# cap_sense.net
KiCad netlist of a schematic drawn in Altium Designer
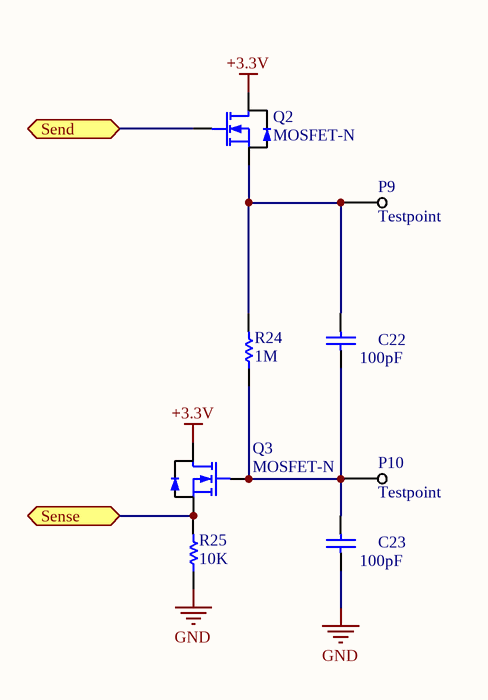
[diagram p0: cap_sense.SchDoc]

(export (version "E")
  (design (tool "Eeschema 10.0.6"))
  (components
    (comp (ref "C22")
      (value "100pF")
      (footprint "Miscellaneous Devices:1608[0603]")
      (description "Capacitor")
      (fields (field (name "Comment") "Cap") (field (name "PUBLISHER") "Altium Limited"))
      (libsource (lib "Schematic Lib") (part "Cap"))
    )
    (comp (ref "C23")
      (value "100pF")
      (footprint "Miscellaneous Devices:1608[0603]")
      (description "Capacitor")
      (fields (field (name "Comment") "Cap") (field (name "PUBLISHER") "Altium Limited"))
      (libsource (lib "Schematic Lib") (part "Cap"))
    )
    (comp (ref "P9")
      (value "Testpoint")
      (footprint "ELE3PRO_2012:Testpoint")
      (libsource (lib "Schematic Lib") (part "Testpoint"))
    )
    (comp (ref "P10")
      (value "Testpoint")
      (footprint "ELE3PRO_2012:Testpoint")
      (libsource (lib "Schematic Lib") (part "Testpoint"))
    )
    (comp (ref "Q2")
      (value "MOSFET-N")
      (footprint "ELE3PRO_2012:SOT23")
      (description "N-Channel MOSFET")
      (fields (field (name "PUBLISHER") "Altium Limited"))
      (libsource (lib "Schlib1") (part "MOSFET-N"))
    )
    (comp (ref "Q3")
      (value "MOSFET-N")
      (footprint "ELE3PRO_2012:SOT23")
      (description "N-Channel MOSFET")
      (fields (field (name "PUBLISHER") "Altium Limited"))
      (libsource (lib "Schlib1") (part "MOSFET-N"))
    )
    (comp (ref "R24")
      (value "1M")
      (footprint "J1-0603")
      (description "Resistor 0805")
      (fields (field (name "Comment") "Res") (field (name "PUBLISHER") "Altium Limited"))
      (libsource (lib "Schematic Lib") (part "Res"))
    )
    (comp (ref "R25")
      (value "10K")
      (footprint "J1-0603")
      (description "Resistor 0805")
      (fields (field (name "Comment") "Res") (field (name "PUBLISHER") "Altium Limited"))
      (libsource (lib "Schematic Lib") (part "Res"))
    )
  )
  (nets
    (net (code "1") (name "+3.3V") (class "Default")
      (node (ref "Q2") (pin "3") (pinfunction "D_3") (pintype "passive"))
      (node (ref "Q3") (pin "3") (pinfunction "D_3") (pintype "passive"))
    )
    (net (code "2") (name "/Send") (class "Default")
      (node (ref "Q2") (pin "1") (pinfunction "G_1") (pintype "passive"))
    )
    (net (code "3") (name "/Sense") (class "Default")
      (node (ref "Q3") (pin "2") (pinfunction "S_2") (pintype "passive"))
      (node (ref "R25") (pin "2") (pinfunction "2_2") (pintype "passive"))
    )
    (net (code "4") (name "GND") (class "Default")
      (node (ref "C23") (pin "2") (pinfunction "2_2") (pintype "passive"))
      (node (ref "R25") (pin "1") (pinfunction "1_1") (pintype "passive"))
    )
    (net (code "5") (name "Net-(Q2-S)") (class "Default")
      (node (ref "C22") (pin "1") (pinfunction "1_1") (pintype "passive"))
      (node (ref "P9") (pin "1") (pinfunction "1_1") (pintype "passive"))
      (node (ref "Q2") (pin "2") (pinfunction "S_2") (pintype "passive"))
      (node (ref "R24") (pin "2") (pinfunction "2_2") (pintype "passive"))
    )
    (net (code "6") (name "Net-(Q3-G)") (class "Default")
      (node (ref "C22") (pin "2") (pinfunction "2_2") (pintype "passive"))
      (node (ref "C23") (pin "1") (pinfunction "1_1") (pintype "passive"))
      (node (ref "P10") (pin "1") (pinfunction "1_1") (pintype "passive"))
      (node (ref "Q3") (pin "1") (pinfunction "G_1") (pintype "passive"))
      (node (ref "R24") (pin "1") (pinfunction "1_1") (pintype "passive"))
    )
  )
)
